# top.net
KiCad netlist of a schematic drawn in Altium Designer
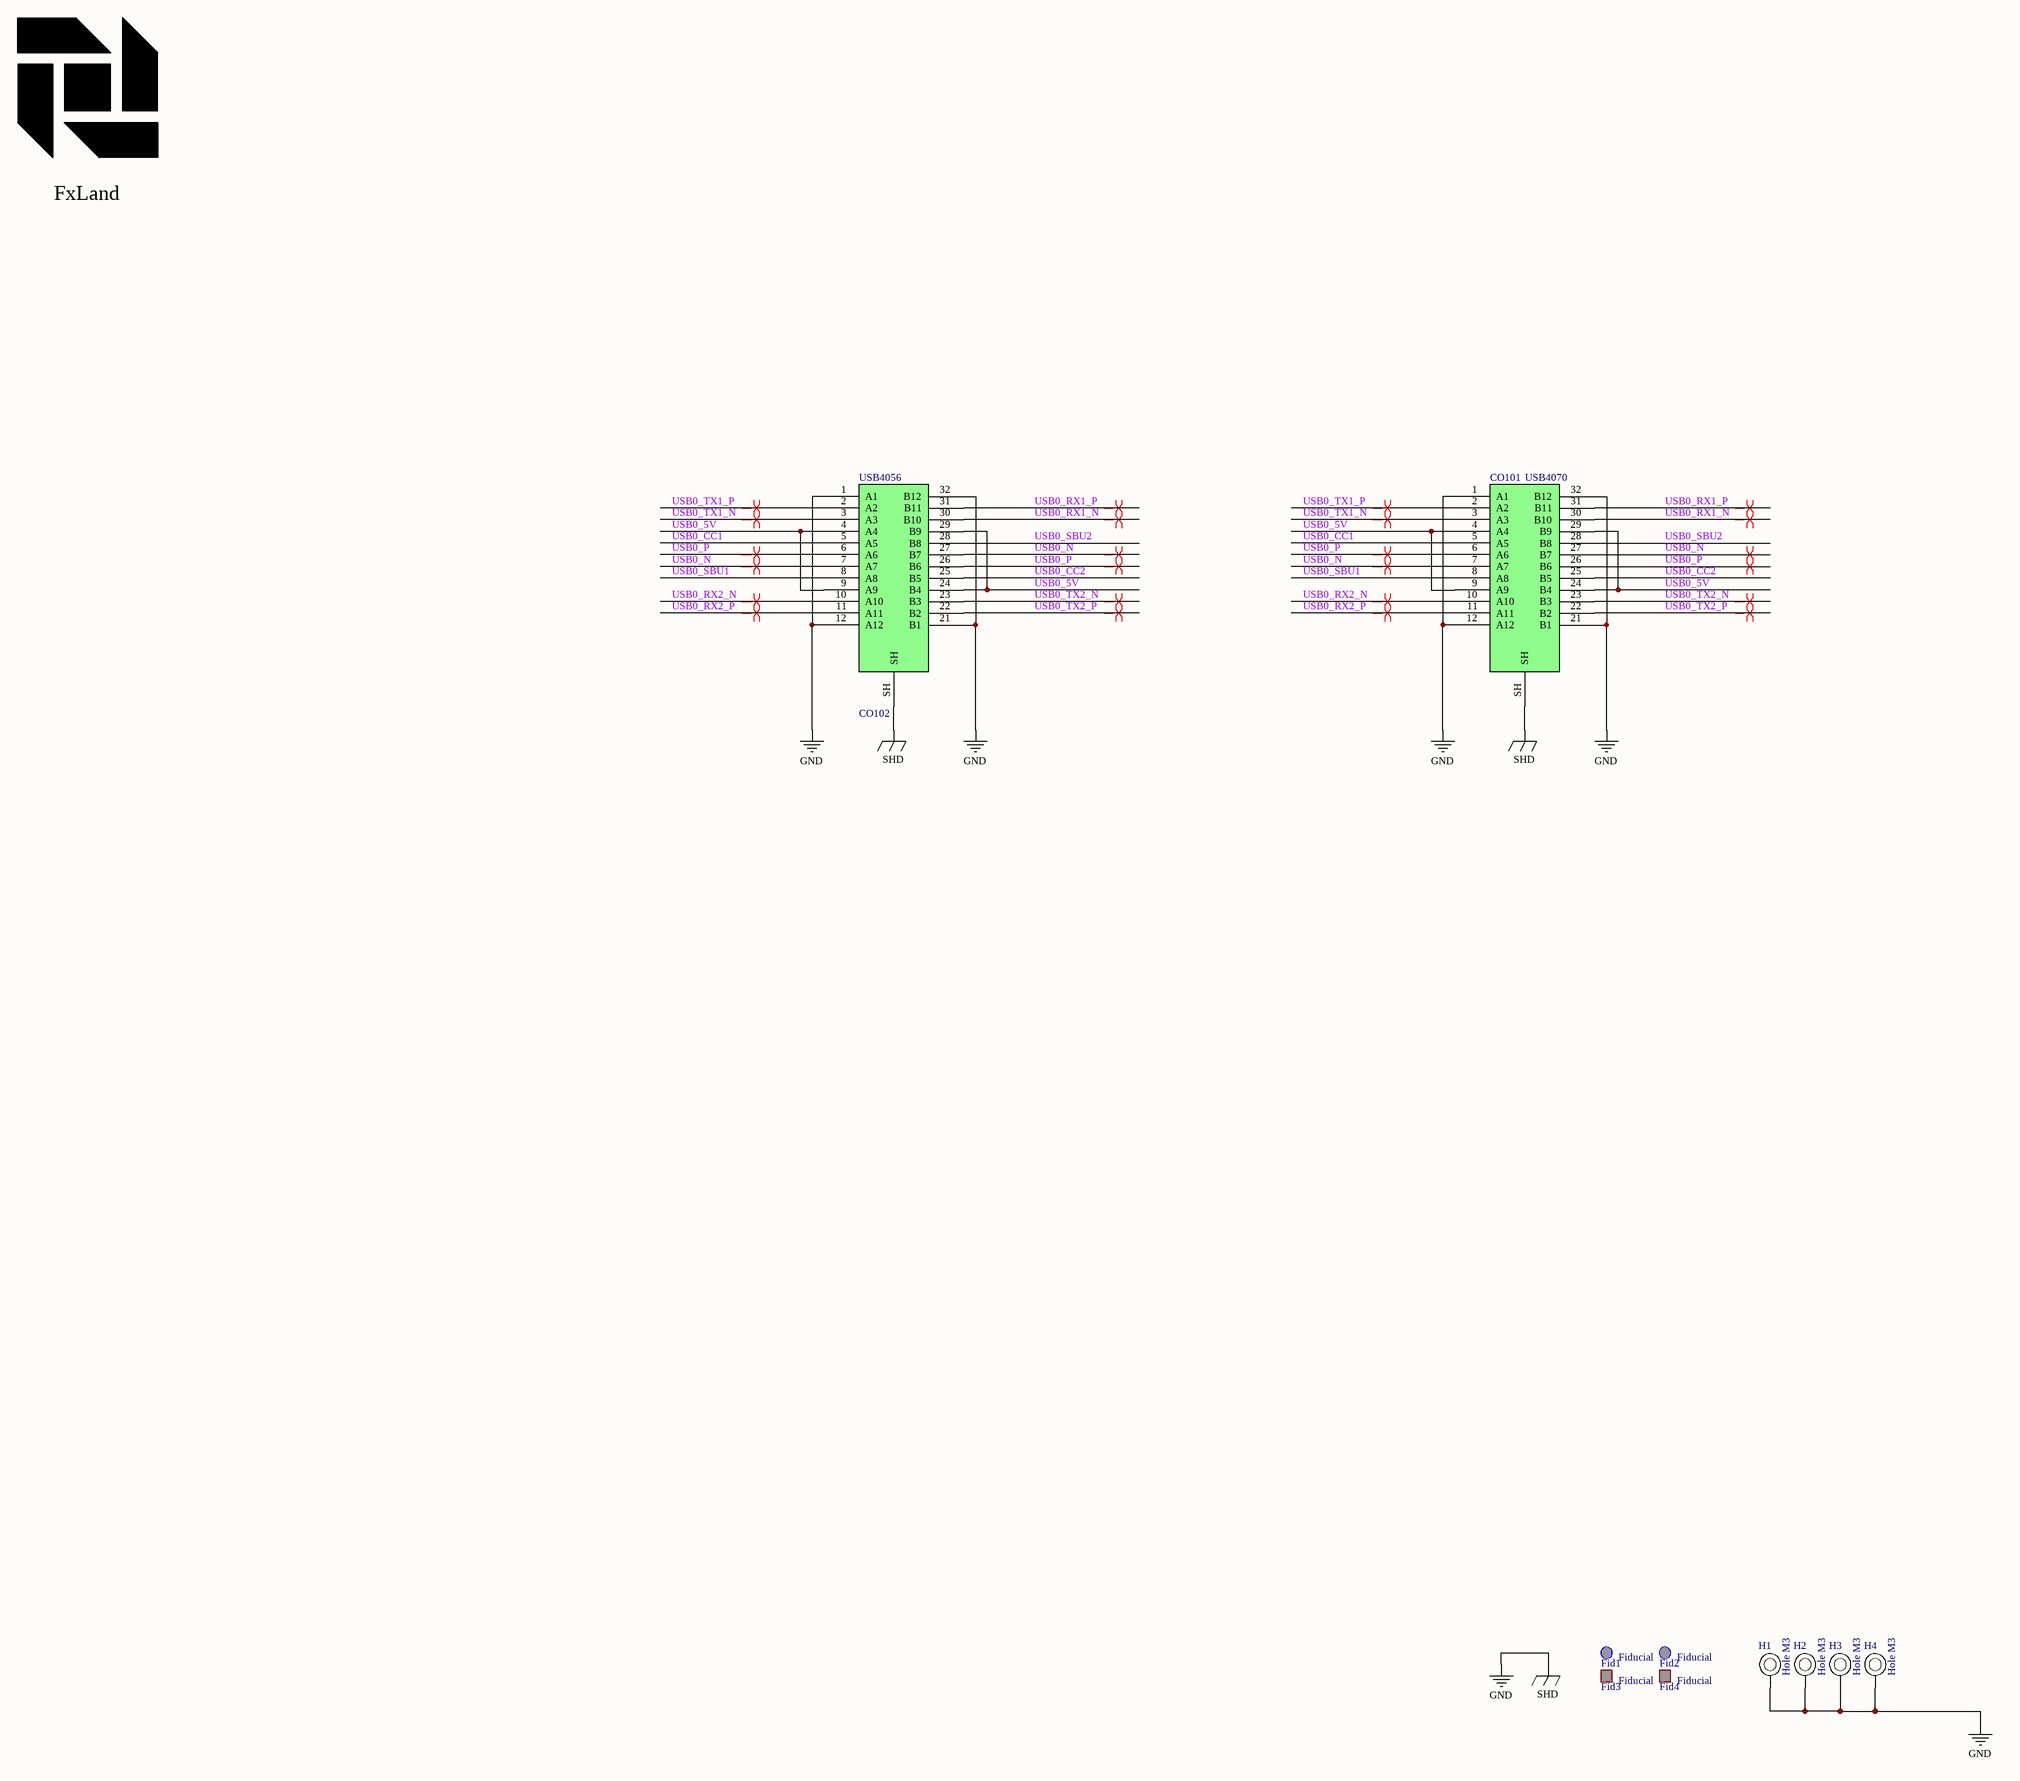
[diagram p0: top.SchDoc]

(export (version "E")
  (design (tool "Eeschema 10.0.6"))
  (components
    (comp (ref "CO101")
      (value "USB4070")
      (footprint "USB4070-30-C")
      (description "USB4070-30-C")
      (fields (field (name "REFVAL") "USB4070") (field (name "PART NUMBER") "CO0021"))
      (libsource (lib "GTS_Database") (part "USB-CC"))
    )
    (comp (ref "CO102")
      (value "USB4056")
      (footprint "USB4056-03-A")
      (description "USB C connector Receptacle Horizontal")
      (fields
        (field (name "REFVAL") "USB4056")
        (field (name "PART NUMBER") "CO0030")
        (field (name "MANFACTPART") "USB4056-03-A")
      )
      (libsource (lib "") (part "USB-CC_1"))
    )
    (comp (ref "Fid1")
      (value "Fiducial")
      (footprint "FidR_1.0mm")
      (description "Fiducial Round 1mm")
      (fields (field (name "REFVAL") "Fiducial") (field (name "PART NUMBER") "ME0011"))
      (libsource (lib "GTS_Database") (part "FidR_1.0mm"))
    )
    (comp (ref "Fid2")
      (value "Fiducial")
      (footprint "FidR_1.0mm")
      (description "Fiducial Round 1mm")
      (fields (field (name "REFVAL") "Fiducial") (field (name "PART NUMBER") "ME0011"))
      (libsource (lib "GTS_Database") (part "FidR_1.0mm"))
    )
    (comp (ref "Fid3")
      (value "Fiducial")
      (footprint "FidS_1.0mm")
      (description "Fiducial Sqaure 1mm")
      (fields (field (name "REFVAL") "Fiducial") (field (name "PART NUMBER") "ME0012"))
      (libsource (lib "GTS_Database") (part "FidS_1.0mm"))
    )
    (comp (ref "Fid4")
      (value "Fiducial")
      (footprint "FidS_1.0mm")
      (description "Fiducial Sqaure 1mm")
      (fields (field (name "REFVAL") "Fiducial") (field (name "PART NUMBER") "ME0012"))
      (libsource (lib "GTS_Database") (part "FidS_1.0mm"))
    )
    (comp (ref "H1")
      (value "Hole M3")
      (footprint "HOLE_M3")
      (description "Mounting Hole M3")
      (fields (field (name "REFVAL") "Hole M3") (field (name "PART NUMBER") "ME0001"))
      (libsource (lib "GTS_Database") (part "HOLE"))
    )
    (comp (ref "H2")
      (value "Hole M3")
      (footprint "HOLE_M3")
      (description "Mounting Hole M3")
      (fields (field (name "REFVAL") "Hole M3") (field (name "PART NUMBER") "ME0001"))
      (libsource (lib "GTS_Database") (part "HOLE"))
    )
    (comp (ref "H3")
      (value "Hole M3")
      (footprint "HOLE_M3")
      (description "Mounting Hole M3")
      (fields (field (name "REFVAL") "Hole M3") (field (name "PART NUMBER") "ME0001"))
      (libsource (lib "GTS_Database") (part "HOLE"))
    )
    (comp (ref "H4")
      (value "Hole M3")
      (footprint "HOLE_M3")
      (description "Mounting Hole M3")
      (fields (field (name "REFVAL") "Hole M3") (field (name "PART NUMBER") "ME0001"))
      (libsource (lib "GTS_Database") (part "HOLE"))
    )
    (comp (ref "Logo FxLand")
      (value "FxLand")
      (footprint "Logo_FxLand_3")
      (description "Logo FxLand 3")
      (fields (field (name "PART NUMBER") "ME0008"))
      (libsource (lib "GTS_Database") (part "Logo_FxLand_2"))
    )
  )
  (nets
    (net (code "1") (name "/USB0_5V") (class "Default")
      (node (ref "CO101") (pin "24") (pinfunction "B4_24") (pintype "passive"))
      (node (ref "CO101") (pin "29") (pinfunction "B9_29") (pintype "passive"))
      (node (ref "CO101") (pin "4") (pinfunction "A4_4") (pintype "passive"))
      (node (ref "CO101") (pin "9") (pinfunction "A9_9") (pintype "passive"))
      (node (ref "CO102") (pin "24") (pinfunction "B4_24") (pintype "passive"))
      (node (ref "CO102") (pin "29") (pinfunction "B9_29") (pintype "passive"))
      (node (ref "CO102") (pin "4") (pinfunction "A4_4") (pintype "passive"))
      (node (ref "CO102") (pin "9") (pinfunction "A9_9") (pintype "passive"))
    )
    (net (code "2") (name "/USB0_CC1") (class "Default")
      (node (ref "CO101") (pin "5") (pinfunction "A5_5") (pintype "passive"))
      (node (ref "CO102") (pin "5") (pinfunction "A5_5") (pintype "passive"))
    )
    (net (code "3") (name "/USB0_CC2") (class "Default")
      (node (ref "CO101") (pin "25") (pinfunction "B5_25") (pintype "passive"))
      (node (ref "CO102") (pin "25") (pinfunction "B5_25") (pintype "passive"))
    )
    (net (code "4") (name "/USB0_N") (class "Default")
      (node (ref "CO101") (pin "27") (pinfunction "B7_27") (pintype "passive"))
      (node (ref "CO101") (pin "7") (pinfunction "A7_7") (pintype "passive"))
      (node (ref "CO102") (pin "27") (pinfunction "B7_27") (pintype "passive"))
      (node (ref "CO102") (pin "7") (pinfunction "A7_7") (pintype "passive"))
    )
    (net (code "5") (name "/USB0_P") (class "Default")
      (node (ref "CO101") (pin "26") (pinfunction "B6_26") (pintype "passive"))
      (node (ref "CO101") (pin "6") (pinfunction "A6_6") (pintype "passive"))
      (node (ref "CO102") (pin "26") (pinfunction "B6_26") (pintype "passive"))
      (node (ref "CO102") (pin "6") (pinfunction "A6_6") (pintype "passive"))
    )
    (net (code "6") (name "/USB0_RX1_N") (class "Default")
      (node (ref "CO101") (pin "30") (pinfunction "B10_30") (pintype "passive"))
      (node (ref "CO102") (pin "30") (pinfunction "B10_30") (pintype "passive"))
    )
    (net (code "7") (name "/USB0_RX1_P") (class "Default")
      (node (ref "CO101") (pin "31") (pinfunction "B11_31") (pintype "passive"))
      (node (ref "CO102") (pin "31") (pinfunction "B11_31") (pintype "passive"))
    )
    (net (code "8") (name "/USB0_RX2_N") (class "Default")
      (node (ref "CO101") (pin "10") (pinfunction "A10_10") (pintype "passive"))
      (node (ref "CO102") (pin "10") (pinfunction "A10_10") (pintype "passive"))
    )
    (net (code "9") (name "/USB0_RX2_P") (class "Default")
      (node (ref "CO101") (pin "11") (pinfunction "A11_11") (pintype "passive"))
      (node (ref "CO102") (pin "11") (pinfunction "A11_11") (pintype "passive"))
    )
    (net (code "10") (name "/USB0_SBU1") (class "Default")
      (node (ref "CO101") (pin "8") (pinfunction "A8_8") (pintype "passive"))
      (node (ref "CO102") (pin "8") (pinfunction "A8_8") (pintype "passive"))
    )
    (net (code "11") (name "/USB0_SBU2") (class "Default")
      (node (ref "CO101") (pin "28") (pinfunction "B8_28") (pintype "passive"))
      (node (ref "CO102") (pin "28") (pinfunction "B8_28") (pintype "passive"))
    )
    (net (code "12") (name "/USB0_TX1_N") (class "Default")
      (node (ref "CO101") (pin "3") (pinfunction "A3_3") (pintype "passive"))
      (node (ref "CO102") (pin "3") (pinfunction "A3_3") (pintype "passive"))
    )
    (net (code "13") (name "/USB0_TX1_P") (class "Default")
      (node (ref "CO101") (pin "2") (pinfunction "A2_2") (pintype "passive"))
      (node (ref "CO102") (pin "2") (pinfunction "A2_2") (pintype "passive"))
    )
    (net (code "14") (name "/USB0_TX2_N") (class "Default")
      (node (ref "CO101") (pin "23") (pinfunction "B3_23") (pintype "passive"))
      (node (ref "CO102") (pin "23") (pinfunction "B3_23") (pintype "passive"))
    )
    (net (code "15") (name "/USB0_TX2_P") (class "Default")
      (node (ref "CO101") (pin "22") (pinfunction "B2_22") (pintype "passive"))
      (node (ref "CO102") (pin "22") (pinfunction "B2_22") (pintype "passive"))
    )
    (net (code "16") (name "GND") (class "Default")
      (node (ref "CO101") (pin "1") (pinfunction "A1_1") (pintype "passive"))
      (node (ref "CO101") (pin "12") (pinfunction "A12_12") (pintype "passive"))
      (node (ref "CO101") (pin "21") (pinfunction "B1_21") (pintype "passive"))
      (node (ref "CO101") (pin "32") (pinfunction "B12_32") (pintype "passive"))
      (node (ref "CO101") (pin "SH") (pinfunction "SH_SH") (pintype "power_in"))
      (node (ref "CO102") (pin "1") (pinfunction "A1_1") (pintype "passive"))
      (node (ref "CO102") (pin "12") (pinfunction "A12_12") (pintype "passive"))
      (node (ref "CO102") (pin "21") (pinfunction "B1_21") (pintype "passive"))
      (node (ref "CO102") (pin "32") (pinfunction "B12_32") (pintype "passive"))
      (node (ref "CO102") (pin "SH") (pinfunction "SH_SH") (pintype "power_in"))
      (node (ref "H1") (pin "1") (pinfunction "1_1") (pintype "passive"))
      (node (ref "H2") (pin "1") (pinfunction "1_1") (pintype "passive"))
      (node (ref "H3") (pin "1") (pinfunction "1_1") (pintype "passive"))
      (node (ref "H4") (pin "1") (pinfunction "1_1") (pintype "passive"))
    )
  )
)
